# Lichtsteuerung-ESP8266.net
KiCad netlist of a schematic drawn in EAGLE
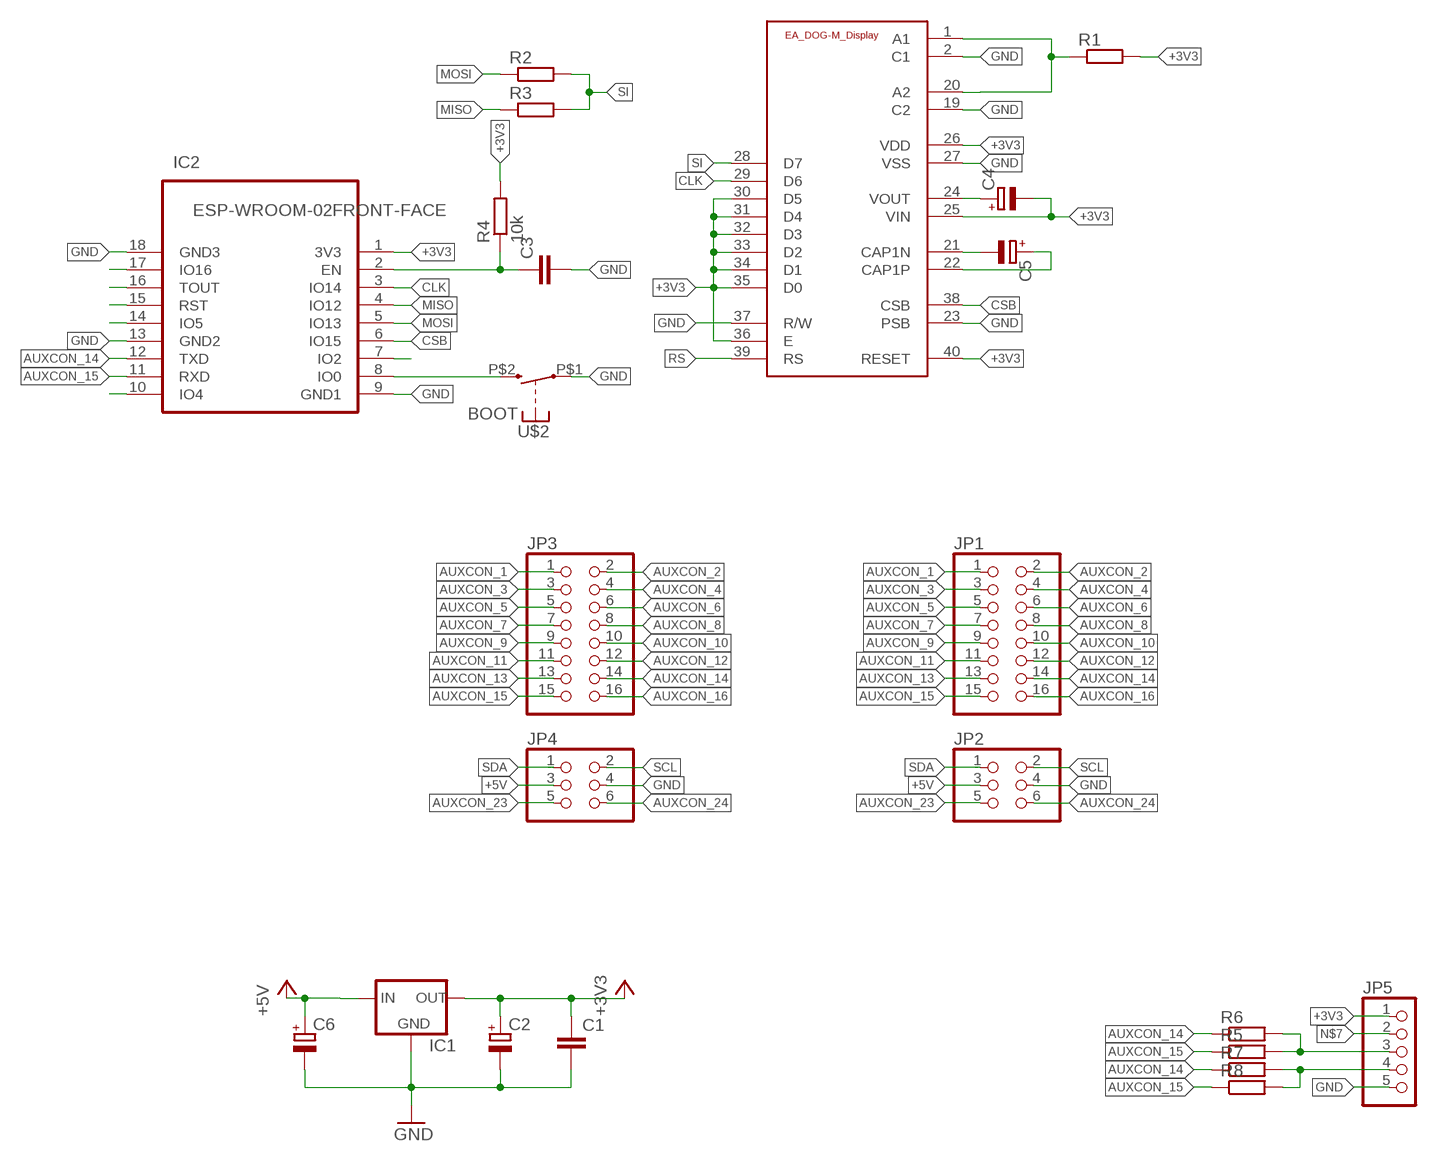
[diagram p0: schematic, sheet 1]

(export (version "E")
  (design (tool "Eeschema 10.0.6"))
  (components
    (comp (ref "C1")
      (value "C-EUC1206")
      (footprint "eagle-import:C1206")
      (libsource (lib "eagle-import") (part "C-EUC1206"))
    )
    (comp (ref "C2")
      (value "CPOL-EUC/6032-28R")
      (footprint "eagle-import:C_6032-28R")
      (libsource (lib "eagle-import") (part "CPOL-EUC/6032-28R"))
    )
    (comp (ref "C3")
      (value "C-EUC1206")
      (footprint "eagle-import:C1206")
      (libsource (lib "eagle-import") (part "C-EUC1206"))
    )
    (comp (ref "C4")
      (value "CPOL-EUSMCA")
      (footprint "eagle-import:SMC_A")
      (libsource (lib "eagle-import") (part "CPOL-EUSMCA"))
    )
    (comp (ref "C5")
      (value "CPOL-EUSMCA")
      (footprint "eagle-import:SMC_A")
      (libsource (lib "eagle-import") (part "CPOL-EUSMCA"))
    )
    (comp (ref "C6")
      (value "CPOL-EUC/6032-28R")
      (footprint "eagle-import:C_6032-28R")
      (libsource (lib "eagle-import") (part "CPOL-EUC/6032-28R"))
    )
    (comp (ref "IC1")
      (value "LM1117")
      (footprint "eagle-import:SOT223")
      (libsource (lib "eagle-import") (part "LM1117"))
    )
    (comp (ref "IC2")
      (value "ESP-WROOM-02FRONT-FACE")
      (footprint "eagle-import:FRONT-FACE")
      (libsource (lib "eagle-import") (part "ESP-WROOM-02FRONT-FACE"))
    )
    (comp (ref "JP1")
      (value "PINHD-2X8")
      (footprint "eagle-import:2X08")
      (libsource (lib "eagle-import") (part "PINHD-2X8"))
    )
    (comp (ref "JP2")
      (value "PINHD-2X3")
      (footprint "eagle-import:2X03")
      (libsource (lib "eagle-import") (part "PINHD-2X3"))
    )
    (comp (ref "JP3")
      (value "PINHD-2X8")
      (footprint "eagle-import:2X08")
      (libsource (lib "eagle-import") (part "PINHD-2X8"))
    )
    (comp (ref "JP4")
      (value "PINHD-2X3")
      (footprint "eagle-import:2X03")
      (libsource (lib "eagle-import") (part "PINHD-2X3"))
    )
    (comp (ref "JP5")
      (value "PINHD-1X5")
      (footprint "eagle-import:1X05")
      (libsource (lib "eagle-import") (part "PINHD-1X5"))
    )
    (comp (ref "R1")
      (value "R-EU_R1206")
      (footprint "eagle-import:R1206")
      (libsource (lib "eagle-import") (part "resistor_R-EU_R1206"))
    )
    (comp (ref "R2")
      (value "R-EU_R1206")
      (footprint "eagle-import:R1206")
      (libsource (lib "eagle-import") (part "R-EU_R1206"))
    )
    (comp (ref "R3")
      (value "R-EU_R1206")
      (footprint "eagle-import:R1206")
      (libsource (lib "eagle-import") (part "R-EU_R1206"))
    )
    (comp (ref "R4")
      (value "10k")
      (footprint "eagle-import:R1206")
      (libsource (lib "eagle-import") (part "R-EU_R1206"))
    )
    (comp (ref "R5")
      (value "R-EU_R1206")
      (footprint "eagle-import:R1206")
      (libsource (lib "eagle-import") (part "R-EU_R1206"))
    )
    (comp (ref "R6")
      (value "R-EU_R1206")
      (footprint "eagle-import:R1206")
      (libsource (lib "eagle-import") (part "R-EU_R1206"))
    )
    (comp (ref "R7")
      (value "R-EU_R1206")
      (footprint "eagle-import:R1206")
      (libsource (lib "eagle-import") (part "R-EU_R1206"))
    )
    (comp (ref "R8")
      (value "R-EU_R1206")
      (footprint "eagle-import:R1206")
      (libsource (lib "eagle-import") (part "R-EU_R1206"))
    )
    (comp (ref "U$1")
      (value "EA_DOG-M_DISPLAY")
      (footprint "eagle-import:E_DOG-M_DISPLAY")
      (libsource (lib "eagle-import") (part "EA_DOG-M_DISPLAY"))
    )
    (comp (ref "U$2")
      (value "BOOT")
      (footprint "eagle-import:SKPM")
      (libsource (lib "eagle-import") (part "ALPSSKPM"))
    )
  )
  (nets
    (net (code "1") (name "+3V3") (class "Default")
      (node (ref "C1") (pin "1") (pinfunction "1_1") (pintype "passive"))
      (node (ref "C2") (pin "+") (pinfunction "+_+") (pintype "passive"))
      (node (ref "C4") (pin "-") (pinfunction "-_-") (pintype "passive"))
      (node (ref "IC1") (pin "2") (pinfunction "OUT_2") (pintype "passive"))
      (node (ref "IC2") (pin "1") (pinfunction "3V3_1") (pintype "power_in"))
      (node (ref "JP5") (pin "1") (pinfunction "1_1") (pintype "passive"))
      (node (ref "R1") (pin "2") (pinfunction "2_2") (pintype "passive"))
      (node (ref "R4") (pin "2") (pinfunction "2_2") (pintype "passive"))
      (node (ref "U$1") (pin "25") (pinfunction "VIN_25") (pintype "bidirectional"))
      (node (ref "U$1") (pin "26") (pinfunction "VDD_26") (pintype "power_in"))
      (node (ref "U$1") (pin "30") (pinfunction "D5_30") (pintype "bidirectional"))
      (node (ref "U$1") (pin "31") (pinfunction "D4_31") (pintype "bidirectional"))
      (node (ref "U$1") (pin "32") (pinfunction "D3_32") (pintype "bidirectional"))
      (node (ref "U$1") (pin "33") (pinfunction "D2_33") (pintype "bidirectional"))
      (node (ref "U$1") (pin "34") (pinfunction "D1_34") (pintype "bidirectional"))
      (node (ref "U$1") (pin "35") (pinfunction "D0_35") (pintype "bidirectional"))
      (node (ref "U$1") (pin "36") (pinfunction "E_36") (pintype "bidirectional"))
      (node (ref "U$1") (pin "40") (pinfunction "RESET_40") (pintype "bidirectional"))
    )
    (net (code "2") (name "+5V") (class "Default")
      (node (ref "C6") (pin "+") (pinfunction "+_+") (pintype "passive"))
      (node (ref "IC1") (pin "3") (pinfunction "IN_3") (pintype "input"))
      (node (ref "JP2") (pin "3") (pinfunction "3_3") (pintype "passive"))
      (node (ref "JP4") (pin "3") (pinfunction "3_3") (pintype "passive"))
    )
    (net (code "3") (name "AUXCON_1") (class "Default")
      (node (ref "JP1") (pin "1") (pinfunction "1_1") (pintype "passive"))
      (node (ref "JP3") (pin "1") (pinfunction "1_1") (pintype "passive"))
    )
    (net (code "4") (name "AUXCON_2") (class "Default")
      (node (ref "JP1") (pin "2") (pinfunction "2_2") (pintype "passive"))
      (node (ref "JP3") (pin "2") (pinfunction "2_2") (pintype "passive"))
    )
    (net (code "5") (name "AUXCON_3") (class "Default")
      (node (ref "JP1") (pin "3") (pinfunction "3_3") (pintype "passive"))
      (node (ref "JP3") (pin "3") (pinfunction "3_3") (pintype "passive"))
    )
    (net (code "6") (name "AUXCON_4") (class "Default")
      (node (ref "JP1") (pin "4") (pinfunction "4_4") (pintype "passive"))
      (node (ref "JP3") (pin "4") (pinfunction "4_4") (pintype "passive"))
    )
    (net (code "7") (name "AUXCON_5") (class "Default")
      (node (ref "JP1") (pin "5") (pinfunction "5_5") (pintype "passive"))
      (node (ref "JP3") (pin "5") (pinfunction "5_5") (pintype "passive"))
    )
    (net (code "8") (name "AUXCON_6") (class "Default")
      (node (ref "JP1") (pin "6") (pinfunction "6_6") (pintype "passive"))
      (node (ref "JP3") (pin "6") (pinfunction "6_6") (pintype "passive"))
    )
    (net (code "9") (name "AUXCON_7") (class "Default")
      (node (ref "JP1") (pin "7") (pinfunction "7_7") (pintype "passive"))
      (node (ref "JP3") (pin "7") (pinfunction "7_7") (pintype "passive"))
    )
    (net (code "10") (name "AUXCON_8") (class "Default")
      (node (ref "JP1") (pin "8") (pinfunction "8_8") (pintype "passive"))
      (node (ref "JP3") (pin "8") (pinfunction "8_8") (pintype "passive"))
    )
    (net (code "11") (name "AUXCON_9") (class "Default")
      (node (ref "JP1") (pin "9") (pinfunction "9_9") (pintype "passive"))
      (node (ref "JP3") (pin "9") (pinfunction "9_9") (pintype "passive"))
    )
    (net (code "12") (name "AUXCON_10") (class "Default")
      (node (ref "JP1") (pin "10") (pinfunction "10_10") (pintype "passive"))
      (node (ref "JP3") (pin "10") (pinfunction "10_10") (pintype "passive"))
    )
    (net (code "13") (name "AUXCON_11") (class "Default")
      (node (ref "JP1") (pin "11") (pinfunction "11_11") (pintype "passive"))
      (node (ref "JP3") (pin "11") (pinfunction "11_11") (pintype "passive"))
    )
    (net (code "14") (name "AUXCON_12") (class "Default")
      (node (ref "JP1") (pin "12") (pinfunction "12_12") (pintype "passive"))
      (node (ref "JP3") (pin "12") (pinfunction "12_12") (pintype "passive"))
    )
    (net (code "15") (name "AUXCON_13") (class "Default")
      (node (ref "JP1") (pin "13") (pinfunction "13_13") (pintype "passive"))
      (node (ref "JP3") (pin "13") (pinfunction "13_13") (pintype "passive"))
    )
    (net (code "16") (name "AUXCON_14") (class "Default")
      (node (ref "IC2") (pin "12") (pinfunction "TXD_12") (pintype "bidirectional"))
      (node (ref "JP1") (pin "14") (pinfunction "14_14") (pintype "passive"))
      (node (ref "JP3") (pin "14") (pinfunction "14_14") (pintype "passive"))
      (node (ref "R6") (pin "1") (pinfunction "1_1") (pintype "passive"))
      (node (ref "R7") (pin "1") (pinfunction "1_1") (pintype "passive"))
    )
    (net (code "17") (name "AUXCON_15") (class "Default")
      (node (ref "IC2") (pin "11") (pinfunction "RXD_11") (pintype "bidirectional"))
      (node (ref "JP1") (pin "15") (pinfunction "15_15") (pintype "passive"))
      (node (ref "JP3") (pin "15") (pinfunction "15_15") (pintype "passive"))
      (node (ref "R5") (pin "1") (pinfunction "1_1") (pintype "passive"))
      (node (ref "R8") (pin "1") (pinfunction "1_1") (pintype "passive"))
    )
    (net (code "18") (name "AUXCON_16") (class "Default")
      (node (ref "JP1") (pin "16") (pinfunction "16_16") (pintype "passive"))
      (node (ref "JP3") (pin "16") (pinfunction "16_16") (pintype "passive"))
    )
    (net (code "19") (name "AUXCON_23") (class "Default")
      (node (ref "JP2") (pin "5") (pinfunction "5_5") (pintype "passive"))
      (node (ref "JP4") (pin "5") (pinfunction "5_5") (pintype "passive"))
    )
    (net (code "20") (name "AUXCON_24") (class "Default")
      (node (ref "JP2") (pin "6") (pinfunction "6_6") (pintype "passive"))
      (node (ref "JP4") (pin "6") (pinfunction "6_6") (pintype "passive"))
    )
    (net (code "21") (name "CLK") (class "Default")
      (node (ref "IC2") (pin "3") (pinfunction "IO14_3") (pintype "bidirectional"))
      (node (ref "U$1") (pin "29") (pinfunction "D6_29") (pintype "bidirectional"))
    )
    (net (code "22") (name "CSB") (class "Default")
      (node (ref "IC2") (pin "6") (pinfunction "IO15_6") (pintype "bidirectional"))
      (node (ref "U$1") (pin "38") (pinfunction "CSB_38") (pintype "bidirectional"))
    )
    (net (code "23") (name "GND") (class "Default")
      (node (ref "C1") (pin "2") (pinfunction "2_2") (pintype "passive"))
      (node (ref "C2") (pin "-") (pinfunction "-_-") (pintype "passive"))
      (node (ref "C3") (pin "2") (pinfunction "2_2") (pintype "passive"))
      (node (ref "C6") (pin "-") (pinfunction "-_-") (pintype "passive"))
      (node (ref "IC1") (pin "1") (pinfunction "GND_1") (pintype "input"))
      (node (ref "IC2") (pin "13") (pinfunction "GND2_13") (pintype "power_in"))
      (node (ref "IC2") (pin "18") (pinfunction "GND3_18") (pintype "power_in"))
      (node (ref "IC2") (pin "9") (pinfunction "GND1_9") (pintype "power_in"))
      (node (ref "JP2") (pin "4") (pinfunction "4_4") (pintype "passive"))
      (node (ref "JP4") (pin "4") (pinfunction "4_4") (pintype "passive"))
      (node (ref "JP5") (pin "5") (pinfunction "5_5") (pintype "passive"))
      (node (ref "U$1") (pin "19") (pinfunction "C2_19") (pintype "bidirectional"))
      (node (ref "U$1") (pin "2") (pinfunction "C1_2") (pintype "bidirectional"))
      (node (ref "U$1") (pin "23") (pinfunction "PSB_23") (pintype "bidirectional"))
      (node (ref "U$1") (pin "27") (pinfunction "VSS_27") (pintype "power_in"))
      (node (ref "U$1") (pin "37") (pinfunction "R/W_37") (pintype "bidirectional"))
      (node (ref "U$2") (pin "P$1") (pinfunction "P_P$1") (pintype "passive"))
    )
    (net (code "24") (name "MISO") (class "Default")
      (node (ref "IC2") (pin "4") (pinfunction "IO12_4") (pintype "bidirectional"))
      (node (ref "R3") (pin "1") (pinfunction "1_1") (pintype "passive"))
    )
    (net (code "25") (name "MOSI") (class "Default")
      (node (ref "IC2") (pin "5") (pinfunction "IO13_5") (pintype "bidirectional"))
      (node (ref "R2") (pin "1") (pinfunction "1_1") (pintype "passive"))
    )
    (net (code "26") (name "N$7") (class "Default")
      (node (ref "JP5") (pin "2") (pinfunction "2_2") (pintype "passive"))
    )
    (net (code "27") (name "Net-(IC2-EN)") (class "Default")
      (node (ref "C3") (pin "1") (pinfunction "1_1") (pintype "passive"))
      (node (ref "IC2") (pin "2") (pinfunction "EN_2") (pintype "bidirectional"))
      (node (ref "R4") (pin "1") (pinfunction "1_1") (pintype "passive"))
    )
    (net (code "28") (name "Net-(IC2-IO0)") (class "Default")
      (node (ref "IC2") (pin "8") (pinfunction "IO0_8") (pintype "bidirectional"))
      (node (ref "U$2") (pin "P$2") (pinfunction "S_P$2") (pintype "passive"))
    )
    (net (code "29") (name "Net-(JP5-Pad3)") (class "Default")
      (node (ref "JP5") (pin "3") (pinfunction "3_3") (pintype "passive"))
      (node (ref "R5") (pin "2") (pinfunction "2_2") (pintype "passive"))
      (node (ref "R6") (pin "2") (pinfunction "2_2") (pintype "passive"))
    )
    (net (code "30") (name "Net-(JP5-Pad4)") (class "Default")
      (node (ref "JP5") (pin "4") (pinfunction "4_4") (pintype "passive"))
      (node (ref "R7") (pin "2") (pinfunction "2_2") (pintype "passive"))
      (node (ref "R8") (pin "2") (pinfunction "2_2") (pintype "passive"))
    )
    (net (code "31") (name "Net-(U$1-A1)") (class "Default")
      (node (ref "R1") (pin "1") (pinfunction "1_1") (pintype "passive"))
      (node (ref "U$1") (pin "1") (pinfunction "A1_1") (pintype "bidirectional"))
      (node (ref "U$1") (pin "20") (pinfunction "A2_20") (pintype "bidirectional"))
    )
    (net (code "32") (name "Net-(U$1-CAP1N)") (class "Default")
      (node (ref "C5") (pin "-") (pinfunction "-_-") (pintype "passive"))
      (node (ref "U$1") (pin "21") (pinfunction "CAP1N_21") (pintype "bidirectional"))
    )
    (net (code "33") (name "Net-(U$1-CAP1P)") (class "Default")
      (node (ref "C5") (pin "+") (pinfunction "+_+") (pintype "passive"))
      (node (ref "U$1") (pin "22") (pinfunction "CAP1P_22") (pintype "bidirectional"))
    )
    (net (code "34") (name "Net-(U$1-VOUT)") (class "Default")
      (node (ref "C4") (pin "+") (pinfunction "+_+") (pintype "passive"))
      (node (ref "U$1") (pin "24") (pinfunction "VOUT_24") (pintype "bidirectional"))
    )
    (net (code "35") (name "RS") (class "Default")
      (node (ref "U$1") (pin "39") (pinfunction "RS_39") (pintype "bidirectional"))
    )
    (net (code "36") (name "SCL") (class "Default")
      (node (ref "JP2") (pin "2") (pinfunction "2_2") (pintype "passive"))
      (node (ref "JP4") (pin "2") (pinfunction "2_2") (pintype "passive"))
    )
    (net (code "37") (name "SDA") (class "Default")
      (node (ref "JP2") (pin "1") (pinfunction "1_1") (pintype "passive"))
      (node (ref "JP4") (pin "1") (pinfunction "1_1") (pintype "passive"))
    )
    (net (code "38") (name "SI") (class "Default")
      (node (ref "R2") (pin "2") (pinfunction "2_2") (pintype "passive"))
      (node (ref "R3") (pin "2") (pinfunction "2_2") (pintype "passive"))
      (node (ref "U$1") (pin "28") (pinfunction "D7_28") (pintype "bidirectional"))
    )
    (net (code "39") (name "unconnected-(IC2-IO2-Pad7)") (class "Default")
      (node (ref "IC2") (pin "7") (pinfunction "IO2_7") (pintype "bidirectional"))
    )
    (net (code "40") (name "unconnected-(IC2-IO4-Pad10)") (class "Default")
      (node (ref "IC2") (pin "10") (pinfunction "IO4_10") (pintype "bidirectional"))
    )
    (net (code "41") (name "unconnected-(IC2-IO5-Pad14)") (class "Default")
      (node (ref "IC2") (pin "14") (pinfunction "IO5_14") (pintype "open_collector"))
    )
    (net (code "42") (name "unconnected-(IC2-IO16-Pad17)") (class "Default")
      (node (ref "IC2") (pin "17") (pinfunction "IO16_17") (pintype "bidirectional"))
    )
    (net (code "43") (name "unconnected-(IC2-RST-Pad15)") (class "Default")
      (node (ref "IC2") (pin "15") (pinfunction "RST_15") (pintype "bidirectional"))
    )
    (net (code "44") (name "unconnected-(IC2-TOUT-Pad16)") (class "Default")
      (node (ref "IC2") (pin "16") (pinfunction "TOUT_16") (pintype "bidirectional"))
    )
  )
)
